# WindDir.net
KiCad netlist of a schematic drawn in Altium Designer
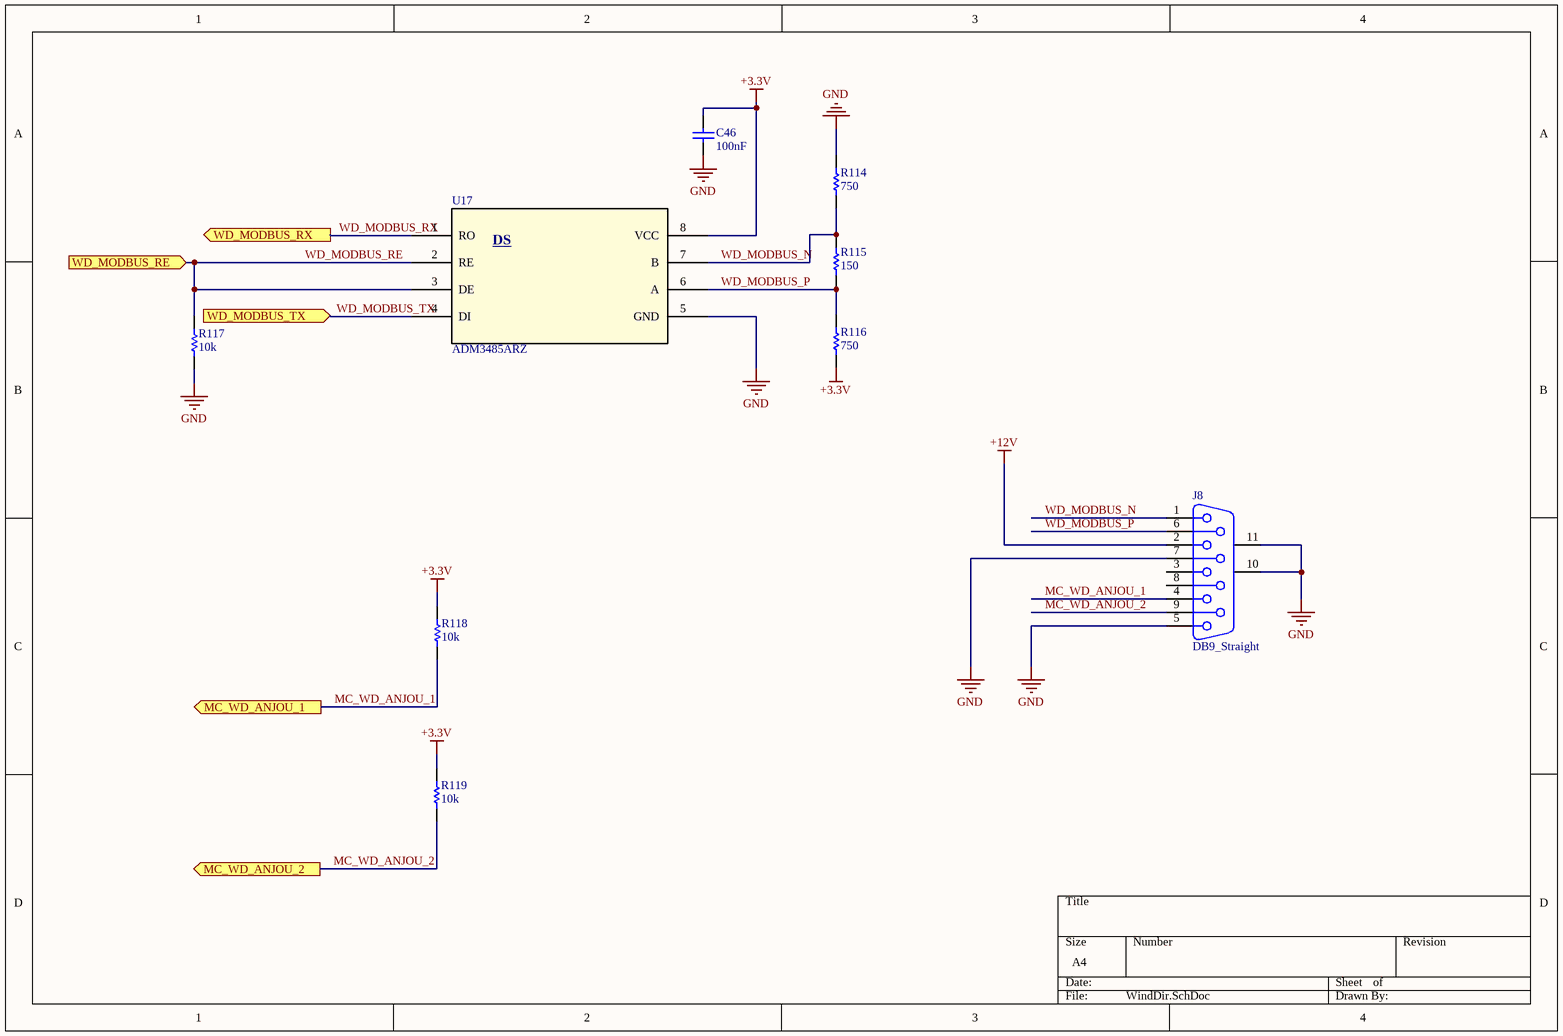
[diagram p0: WindDir.SchDoc]

(export (version "E")
  (design (tool "Eeschema 10.0.6"))
  (components
    (comp (ref "C46")
      (value "100nF")
      (footprint "C-805")
      (description "Capacitor")
      (fields (field (name "Comment") "C-805") (field (name "PUBLISHER") "Altium Limited"))
      (libsource (lib "AfraLIB") (part "C-805"))
    )
    (comp (ref "J8")
      (value "DB9_Straight")
      (footprint "DB9_Straight")
      (description "Receptacle Assembly, 9 Position, Right Angle")
      (fields (field (name "PUBLISHER") "Altium Limited"))
      (libsource (lib "AfraLIB") (part "DB9_Straight"))
    )
    (comp (ref "R114")
      (value "750")
      (footprint "R-805")
      (description "Resistor")
      (fields (field (name "Comment") "R-805"))
      (libsource (lib "AfraLIB") (part "R-805"))
    )
    (comp (ref "R115")
      (value "150")
      (footprint "R-805")
      (description "Resistor")
      (fields (field (name "Comment") "R-805"))
      (libsource (lib "AfraLIB") (part "R-805"))
    )
    (comp (ref "R116")
      (value "750")
      (footprint "R-805")
      (description "Resistor")
      (fields (field (name "Comment") "R-805"))
      (libsource (lib "AfraLIB") (part "R-805"))
    )
    (comp (ref "R117")
      (value "10k")
      (footprint "R-805")
      (description "Resistor")
      (fields (field (name "Comment") "R-805"))
      (libsource (lib "AfraLIB") (part "R-805"))
    )
    (comp (ref "R118")
      (value "10k")
      (footprint "R-805")
      (description "Resistor")
      (fields (field (name "Comment") "R-805"))
      (libsource (lib "AfraLIB") (part "R-805"))
    )
    (comp (ref "R119")
      (value "10k")
      (footprint "R-805")
      (description "Resistor")
      (fields (field (name "Comment") "R-805"))
      (libsource (lib "AfraLIB") (part "R-805"))
    )
    (comp (ref "U17")
      (value "ADM3485ARZ")
      (footprint "R_8")
      (description "No Description Available")
      (fields (field (name "COPYRIGHT") "Copyright (C) 2018 Accelerated Designs. All rights reserved"))
      (libsource (lib "AfraLIB") (part "ADM3485ARZ"))
    )
  )
  (nets
    (net (code "1") (name "+3.3V") (class "Default")
      (node (ref "C46") (pin "2") (pinfunction "2_2") (pintype "passive"))
      (node (ref "R116") (pin "1") (pinfunction "1_1") (pintype "passive"))
      (node (ref "R118") (pin "2") (pinfunction "2_2") (pintype "passive"))
      (node (ref "R119") (pin "2") (pinfunction "2_2") (pintype "passive"))
      (node (ref "U17") (pin "8") (pinfunction "VCC_8") (pintype "passive"))
    )
    (net (code "2") (name "+12V") (class "Default")
      (node (ref "J8") (pin "2") (pinfunction "2_2") (pintype "passive"))
    )
    (net (code "3") (name "/MC_WD_ANJOU_1") (class "Default")
      (node (ref "J8") (pin "4") (pinfunction "4_4") (pintype "passive"))
      (node (ref "R118") (pin "1") (pinfunction "1_1") (pintype "passive"))
    )
    (net (code "4") (name "/MC_WD_ANJOU_2") (class "Default")
      (node (ref "J8") (pin "9") (pinfunction "9_9") (pintype "passive"))
      (node (ref "R119") (pin "1") (pinfunction "1_1") (pintype "passive"))
    )
    (net (code "5") (name "/WD_MODBUS_N") (class "Default")
      (node (ref "J8") (pin "1") (pinfunction "1_1") (pintype "passive"))
      (node (ref "R114") (pin "1") (pinfunction "1_1") (pintype "passive"))
      (node (ref "R115") (pin "2") (pinfunction "2_2") (pintype "passive"))
      (node (ref "U17") (pin "7") (pinfunction "B_7") (pintype "passive"))
    )
    (net (code "6") (name "/WD_MODBUS_P") (class "Default")
      (node (ref "J8") (pin "6") (pinfunction "6_6") (pintype "passive"))
      (node (ref "R115") (pin "1") (pinfunction "1_1") (pintype "passive"))
      (node (ref "R116") (pin "2") (pinfunction "2_2") (pintype "passive"))
      (node (ref "U17") (pin "6") (pinfunction "A_6") (pintype "passive"))
    )
    (net (code "7") (name "/WD_MODBUS_RE") (class "Default")
      (node (ref "R117") (pin "2") (pinfunction "2_2") (pintype "passive"))
      (node (ref "U17") (pin "2") (pinfunction "RE_2") (pintype "passive"))
      (node (ref "U17") (pin "3") (pinfunction "DE_3") (pintype "passive"))
    )
    (net (code "8") (name "/WD_MODBUS_RX") (class "Default")
      (node (ref "U17") (pin "1") (pinfunction "RO_1") (pintype "passive"))
    )
    (net (code "9") (name "/WD_MODBUS_TX") (class "Default")
      (node (ref "U17") (pin "4") (pinfunction "DI_4") (pintype "passive"))
    )
    (net (code "10") (name "GND") (class "Default")
      (node (ref "C46") (pin "1") (pinfunction "1_1") (pintype "passive"))
      (node (ref "J8") (pin "10") (pinfunction "MH1_10") (pintype "passive"))
      (node (ref "J8") (pin "11") (pinfunction "MH2_11") (pintype "passive"))
      (node (ref "J8") (pin "5") (pinfunction "5_5") (pintype "passive"))
      (node (ref "J8") (pin "7") (pinfunction "7_7") (pintype "passive"))
      (node (ref "R114") (pin "2") (pinfunction "2_2") (pintype "passive"))
      (node (ref "R117") (pin "1") (pinfunction "1_1") (pintype "passive"))
      (node (ref "U17") (pin "5") (pinfunction "GND_5") (pintype "passive"))
    )
    (net (code "11") (name "unconnected-(J8-Pad3)") (class "Default")
      (node (ref "J8") (pin "3") (pinfunction "3_3") (pintype "passive"))
    )
    (net (code "12") (name "unconnected-(J8-Pad8)") (class "Default")
      (node (ref "J8") (pin "8") (pinfunction "8_8") (pintype "passive"))
    )
  )
)
